# MIC.net
KiCad netlist of a schematic drawn in Altium Designer
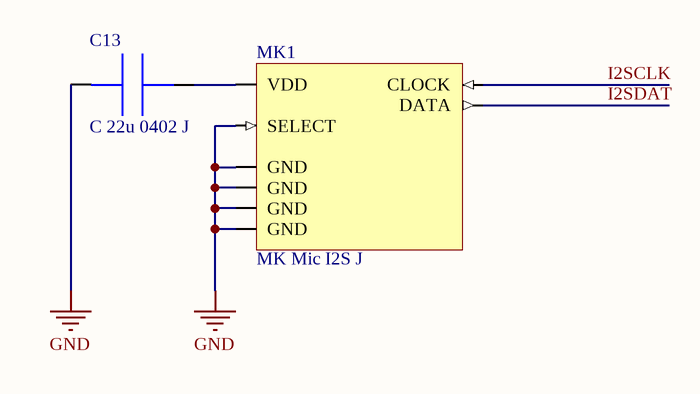
[diagram p0: MIC.SchDoc]

(export (version "E")
  (design (tool "Eeschema 10.0.6"))
  (components
    (comp (ref "C13")
      (value "C 22u 0402 J")
      (footprint "C0402")
      (description "Multi-Layer Ceramic Capacitor 22uF 2.5VDC X6S 20% 0402 Paper T/R GRM155C80E226ME11D")
      (fields
        (field (name "MANUFACTURER") "Murata")
        (field (name "MANUFACTURER PART NUMBER") "GRM155C80E226ME11D")
      )
      (libsource (lib "Schlib1") (part "C 22u 0402 J"))
    )
    (comp (ref "MK1")
      (value "MK Mic I2S J")
      (footprint "MK WMM7040DTHN0")
      (description "WILLSEMI(Will Semicon) SMD MEMS Microphones ROHS WMM7040DTHN0")
      (fields
        (field (name "MANUFACTURER") "WILLSEMI(Will Semicon)")
        (field (name "MANUFACTURER PART NUMBER") "WMM7040DTHN0")
      )
      (libsource (lib "Schlib1") (part "MK Mic I2S J"))
    )
  )
  (nets
    (net (code "1") (name "/I2SCLK") (class "Default")
      (node (ref "MK1") (pin "3") (pinfunction "CLOCK_3") (pintype "input"))
    )
    (net (code "2") (name "/I2SDAT") (class "Default")
      (node (ref "MK1") (pin "4") (pinfunction "DATA_4") (pintype "output"))
    )
    (net (code "3") (name "GND") (class "Default")
      (node (ref "C13") (pin "1") (pinfunction "1_1") (pintype "passive"))
      (node (ref "MK1") (pin "2") (pinfunction "SELECT_2") (pintype "input"))
      (node (ref "MK1") (pin "5") (pinfunction "GND_5") (pintype "power_in"))
      (node (ref "MK1") (pin "6") (pinfunction "GND_6") (pintype "power_in"))
      (node (ref "MK1") (pin "7") (pinfunction "GND_7") (pintype "power_in"))
      (node (ref "MK1") (pin "8") (pinfunction "GND_8") (pintype "power_in"))
    )
    (net (code "4") (name "Net-(MK1-VDD)") (class "Default")
      (node (ref "C13") (pin "2") (pinfunction "2_2") (pintype "passive"))
      (node (ref "MK1") (pin "1") (pinfunction "VDD_1") (pintype "power_in"))
    )
  )
)
